# digifab.net
KiCad netlist of a schematic drawn in EAGLE
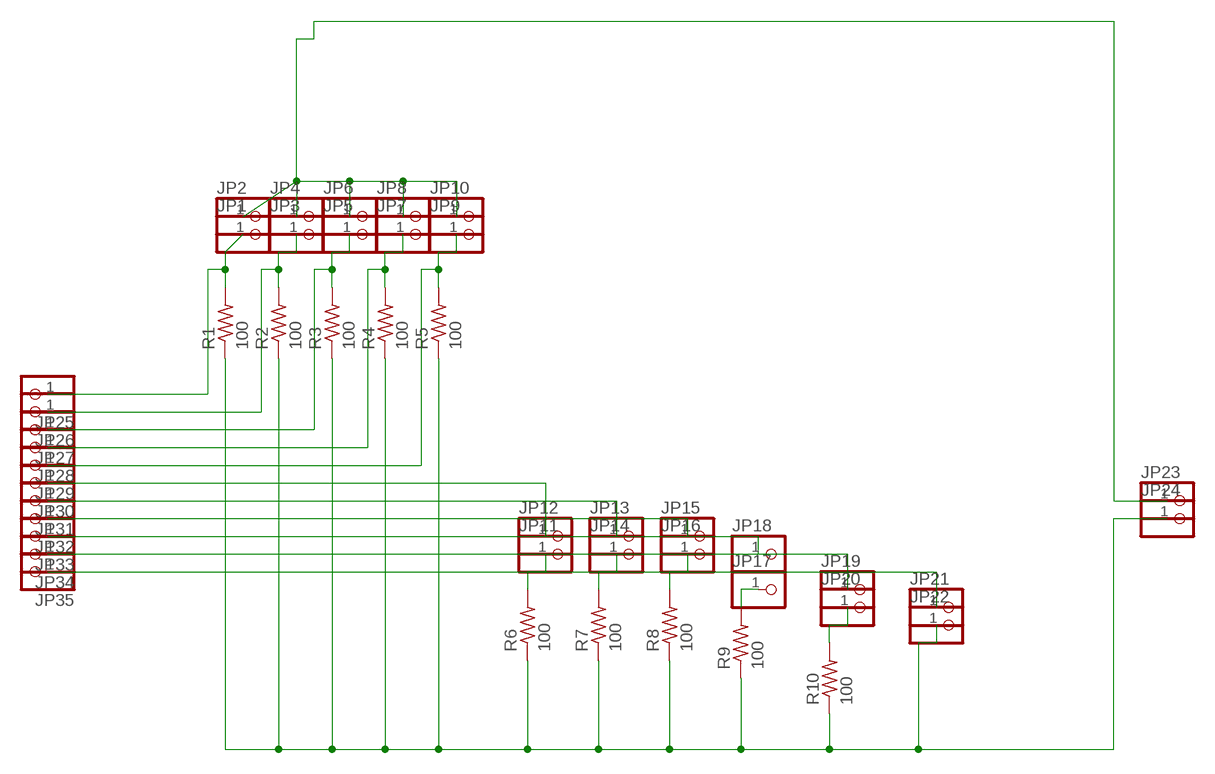
[diagram p0: schematic, sheet 1]

(export (version "E")
  (design (tool "Eeschema 10.0.6"))
  (components
    (comp (ref "JP1")
      (value "PINHD-1X01_2.54-90°")
      (footprint "eagle-import:1X01_90")
      (libsource (lib "eagle-import") (part "PINHD-1X01_2.54-90°"))
    )
    (comp (ref "JP2")
      (value "PINHD-1X01_2.54-90°")
      (footprint "eagle-import:1X01_90")
      (libsource (lib "eagle-import") (part "PINHD-1X01_2.54-90°"))
    )
    (comp (ref "JP3")
      (value "PINHD-1X01_2.54-90°")
      (footprint "eagle-import:1X01_90")
      (libsource (lib "eagle-import") (part "PINHD-1X01_2.54-90°"))
    )
    (comp (ref "JP4")
      (value "PINHD-1X01_2.54-90°")
      (footprint "eagle-import:1X01_90")
      (libsource (lib "eagle-import") (part "PINHD-1X01_2.54-90°"))
    )
    (comp (ref "JP5")
      (value "PINHD-1X01_2.54-90°")
      (footprint "eagle-import:1X01_90")
      (libsource (lib "eagle-import") (part "PINHD-1X01_2.54-90°"))
    )
    (comp (ref "JP6")
      (value "PINHD-1X01_2.54-90°")
      (footprint "eagle-import:1X01_90")
      (libsource (lib "eagle-import") (part "PINHD-1X01_2.54-90°"))
    )
    (comp (ref "JP7")
      (value "PINHD-1X01_2.54-90°")
      (footprint "eagle-import:1X01_90")
      (libsource (lib "eagle-import") (part "PINHD-1X01_2.54-90°"))
    )
    (comp (ref "JP8")
      (value "PINHD-1X01_2.54-90°")
      (footprint "eagle-import:1X01_90")
      (libsource (lib "eagle-import") (part "PINHD-1X01_2.54-90°"))
    )
    (comp (ref "JP9")
      (value "PINHD-1X01_2.54-90°")
      (footprint "eagle-import:1X01_90")
      (libsource (lib "eagle-import") (part "PINHD-1X01_2.54-90°"))
    )
    (comp (ref "JP10")
      (value "PINHD-1X01_2.54-90°")
      (footprint "eagle-import:1X01_90")
      (libsource (lib "eagle-import") (part "PINHD-1X01_2.54-90°"))
    )
    (comp (ref "JP11")
      (value "PINHD-1X01_2.54-90°")
      (footprint "eagle-import:1X01_90")
      (libsource (lib "eagle-import") (part "PINHD-1X01_2.54-90°"))
    )
    (comp (ref "JP12")
      (value "PINHD-1X01_2.54-90°")
      (footprint "eagle-import:1X01_90")
      (libsource (lib "eagle-import") (part "PINHD-1X01_2.54-90°"))
    )
    (comp (ref "JP13")
      (value "PINHD-1X01_2.54-90°")
      (footprint "eagle-import:1X01_90")
      (libsource (lib "eagle-import") (part "PINHD-1X01_2.54-90°"))
    )
    (comp (ref "JP14")
      (value "PINHD-1X01_2.54-90°")
      (footprint "eagle-import:1X01_90")
      (libsource (lib "eagle-import") (part "PINHD-1X01_2.54-90°"))
    )
    (comp (ref "JP15")
      (value "PINHD-1X01_2.54-90°")
      (footprint "eagle-import:1X01_90")
      (libsource (lib "eagle-import") (part "PINHD-1X01_2.54-90°"))
    )
    (comp (ref "JP16")
      (value "PINHD-1X01_2.54-90°")
      (footprint "eagle-import:1X01_90")
      (libsource (lib "eagle-import") (part "PINHD-1X01_2.54-90°"))
    )
    (comp (ref "JP17")
      (value "PINHD-1X01_2.54-90°")
      (footprint "eagle-import:1X01_90")
      (libsource (lib "eagle-import") (part "PINHD-1X01_2.54-90°"))
    )
    (comp (ref "JP18")
      (value "PINHD-1X01_2.54-90°")
      (footprint "eagle-import:1X01_90")
      (libsource (lib "eagle-import") (part "PINHD-1X01_2.54-90°"))
    )
    (comp (ref "JP19")
      (value "PINHD-1X01_2.54-90°")
      (footprint "eagle-import:1X01_90")
      (libsource (lib "eagle-import") (part "PINHD-1X01_2.54-90°"))
    )
    (comp (ref "JP20")
      (value "PINHD-1X01_2.54-90°")
      (footprint "eagle-import:1X01_90")
      (libsource (lib "eagle-import") (part "PINHD-1X01_2.54-90°"))
    )
    (comp (ref "JP21")
      (value "PINHD-1X01_2.54-90°")
      (footprint "eagle-import:1X01_90")
      (libsource (lib "eagle-import") (part "PINHD-1X01_2.54-90°"))
    )
    (comp (ref "JP22")
      (value "PINHD-1X01_2.54-90°")
      (footprint "eagle-import:1X01_90")
      (libsource (lib "eagle-import") (part "PINHD-1X01_2.54-90°"))
    )
    (comp (ref "JP23")
      (value "PINHD-1X01_2.54-90°")
      (footprint "eagle-import:1X01_90")
      (libsource (lib "eagle-import") (part "PINHD-1X01_2.54-90°"))
    )
    (comp (ref "JP24")
      (value "PINHD-1X01_2.54-90°")
      (footprint "eagle-import:1X01_90")
      (libsource (lib "eagle-import") (part "PINHD-1X01_2.54-90°"))
    )
    (comp (ref "JP25")
      (value "PINHD-1X01_2.54-90°")
      (footprint "eagle-import:1X01_90")
      (libsource (lib "eagle-import") (part "PINHD-1X01_2.54-90°"))
    )
    (comp (ref "JP26")
      (value "PINHD-1X01_2.54-90°")
      (footprint "eagle-import:1X01_90")
      (libsource (lib "eagle-import") (part "PINHD-1X01_2.54-90°"))
    )
    (comp (ref "JP27")
      (value "PINHD-1X01_2.54-90°")
      (footprint "eagle-import:1X01_90")
      (libsource (lib "eagle-import") (part "PINHD-1X01_2.54-90°"))
    )
    (comp (ref "JP28")
      (value "PINHD-1X01_2.54-90°")
      (footprint "eagle-import:1X01_90")
      (libsource (lib "eagle-import") (part "PINHD-1X01_2.54-90°"))
    )
    (comp (ref "JP29")
      (value "PINHD-1X01_2.54-90°")
      (footprint "eagle-import:1X01_90")
      (libsource (lib "eagle-import") (part "PINHD-1X01_2.54-90°"))
    )
    (comp (ref "JP30")
      (value "PINHD-1X01_2.54-90°")
      (footprint "eagle-import:1X01_90")
      (libsource (lib "eagle-import") (part "PINHD-1X01_2.54-90°"))
    )
    (comp (ref "JP31")
      (value "PINHD-1X01_2.54-90°")
      (footprint "eagle-import:1X01_90")
      (libsource (lib "eagle-import") (part "PINHD-1X01_2.54-90°"))
    )
    (comp (ref "JP32")
      (value "PINHD-1X01_2.54-90°")
      (footprint "eagle-import:1X01_90")
      (libsource (lib "eagle-import") (part "PINHD-1X01_2.54-90°"))
    )
    (comp (ref "JP33")
      (value "PINHD-1X01_2.54-90°")
      (footprint "eagle-import:1X01_90")
      (libsource (lib "eagle-import") (part "PINHD-1X01_2.54-90°"))
    )
    (comp (ref "JP34")
      (value "PINHD-1X01_2.54-90°")
      (footprint "eagle-import:1X01_90")
      (libsource (lib "eagle-import") (part "PINHD-1X01_2.54-90°"))
    )
    (comp (ref "JP35")
      (value "PINHD-1X01_2.54-90°")
      (footprint "eagle-import:1X01_90")
      (libsource (lib "eagle-import") (part "PINHD-1X01_2.54-90°"))
    )
    (comp (ref "R1")
      (value "100")
      (footprint "eagle-import:R1206FAB")
      (libsource (lib "eagle-import") (part "RES-US1206FAB"))
    )
    (comp (ref "R2")
      (value "100")
      (footprint "eagle-import:R1206FAB")
      (libsource (lib "eagle-import") (part "RES-US1206FAB"))
    )
    (comp (ref "R3")
      (value "100")
      (footprint "eagle-import:R1206FAB")
      (libsource (lib "eagle-import") (part "RES-US1206FAB"))
    )
    (comp (ref "R4")
      (value "100")
      (footprint "eagle-import:R1206FAB")
      (libsource (lib "eagle-import") (part "RES-US1206FAB"))
    )
    (comp (ref "R5")
      (value "100")
      (footprint "eagle-import:R1206FAB")
      (libsource (lib "eagle-import") (part "RES-US1206FAB"))
    )
    (comp (ref "R6")
      (value "100")
      (footprint "eagle-import:R1206FAB")
      (libsource (lib "eagle-import") (part "RES-US1206FAB"))
    )
    (comp (ref "R7")
      (value "100")
      (footprint "eagle-import:R1206FAB")
      (libsource (lib "eagle-import") (part "RES-US1206FAB"))
    )
    (comp (ref "R8")
      (value "100")
      (footprint "eagle-import:R1206FAB")
      (libsource (lib "eagle-import") (part "RES-US1206FAB"))
    )
    (comp (ref "R9")
      (value "100")
      (footprint "eagle-import:R1206FAB")
      (libsource (lib "eagle-import") (part "RES-US1206FAB"))
    )
    (comp (ref "R10")
      (value "100")
      (footprint "eagle-import:R1206FAB")
      (libsource (lib "eagle-import") (part "RES-US1206FAB"))
    )
  )
  (nets
    (net (code "1") (name "Net-(JP1-Pad1)") (class "Default")
      (node (ref "JP1") (pin "1") (pinfunction "1_1") (pintype "passive"))
      (node (ref "JP25") (pin "1") (pinfunction "1_1") (pintype "passive"))
      (node (ref "R1") (pin "2") (pinfunction "2_2") (pintype "passive"))
    )
    (net (code "2") (name "Net-(JP10-Pad1)") (class "Default")
      (node (ref "JP10") (pin "1") (pinfunction "1_1") (pintype "passive"))
      (node (ref "JP2") (pin "1") (pinfunction "1_1") (pintype "passive"))
      (node (ref "JP23") (pin "1") (pinfunction "1_1") (pintype "passive"))
      (node (ref "JP4") (pin "1") (pinfunction "1_1") (pintype "passive"))
      (node (ref "JP6") (pin "1") (pinfunction "1_1") (pintype "passive"))
      (node (ref "JP8") (pin "1") (pinfunction "1_1") (pintype "passive"))
    )
    (net (code "3") (name "Net-(JP11-Pad1)") (class "Default")
      (node (ref "JP11") (pin "1") (pinfunction "1_1") (pintype "passive"))
      (node (ref "R6") (pin "2") (pinfunction "2_2") (pintype "passive"))
    )
    (net (code "4") (name "Net-(JP12-Pad1)") (class "Default")
      (node (ref "JP12") (pin "1") (pinfunction "1_1") (pintype "passive"))
      (node (ref "JP30") (pin "1") (pinfunction "1_1") (pintype "passive"))
    )
    (net (code "5") (name "Net-(JP13-Pad1)") (class "Default")
      (node (ref "JP13") (pin "1") (pinfunction "1_1") (pintype "passive"))
      (node (ref "JP31") (pin "1") (pinfunction "1_1") (pintype "passive"))
    )
    (net (code "6") (name "Net-(JP14-Pad1)") (class "Default")
      (node (ref "JP14") (pin "1") (pinfunction "1_1") (pintype "passive"))
      (node (ref "R7") (pin "2") (pinfunction "2_2") (pintype "passive"))
    )
    (net (code "7") (name "Net-(JP15-Pad1)") (class "Default")
      (node (ref "JP15") (pin "1") (pinfunction "1_1") (pintype "passive"))
      (node (ref "JP32") (pin "1") (pinfunction "1_1") (pintype "passive"))
    )
    (net (code "8") (name "Net-(JP16-Pad1)") (class "Default")
      (node (ref "JP16") (pin "1") (pinfunction "1_1") (pintype "passive"))
      (node (ref "R8") (pin "2") (pinfunction "2_2") (pintype "passive"))
    )
    (net (code "9") (name "Net-(JP17-Pad1)") (class "Default")
      (node (ref "JP17") (pin "1") (pinfunction "1_1") (pintype "passive"))
      (node (ref "R9") (pin "2") (pinfunction "2_2") (pintype "passive"))
    )
    (net (code "10") (name "Net-(JP18-Pad1)") (class "Default")
      (node (ref "JP18") (pin "1") (pinfunction "1_1") (pintype "passive"))
      (node (ref "JP33") (pin "1") (pinfunction "1_1") (pintype "passive"))
    )
    (net (code "11") (name "Net-(JP19-Pad1)") (class "Default")
      (node (ref "JP19") (pin "1") (pinfunction "1_1") (pintype "passive"))
      (node (ref "JP34") (pin "1") (pinfunction "1_1") (pintype "passive"))
    )
    (net (code "12") (name "Net-(JP20-Pad1)") (class "Default")
      (node (ref "JP20") (pin "1") (pinfunction "1_1") (pintype "passive"))
      (node (ref "R10") (pin "2") (pinfunction "2_2") (pintype "passive"))
    )
    (net (code "13") (name "Net-(JP21-Pad1)") (class "Default")
      (node (ref "JP21") (pin "1") (pinfunction "1_1") (pintype "passive"))
      (node (ref "JP35") (pin "1") (pinfunction "1_1") (pintype "passive"))
    )
    (net (code "14") (name "Net-(JP22-Pad1)") (class "Default")
      (node (ref "JP22") (pin "1") (pinfunction "1_1") (pintype "passive"))
      (node (ref "JP24") (pin "1") (pinfunction "1_1") (pintype "passive"))
      (node (ref "R1") (pin "1") (pinfunction "1_1") (pintype "passive"))
      (node (ref "R10") (pin "1") (pinfunction "1_1") (pintype "passive"))
      (node (ref "R2") (pin "1") (pinfunction "1_1") (pintype "passive"))
      (node (ref "R3") (pin "1") (pinfunction "1_1") (pintype "passive"))
      (node (ref "R4") (pin "1") (pinfunction "1_1") (pintype "passive"))
      (node (ref "R5") (pin "1") (pinfunction "1_1") (pintype "passive"))
      (node (ref "R6") (pin "1") (pinfunction "1_1") (pintype "passive"))
      (node (ref "R7") (pin "1") (pinfunction "1_1") (pintype "passive"))
      (node (ref "R8") (pin "1") (pinfunction "1_1") (pintype "passive"))
      (node (ref "R9") (pin "1") (pinfunction "1_1") (pintype "passive"))
    )
    (net (code "15") (name "Net-(JP26-Pad1)") (class "Default")
      (node (ref "JP26") (pin "1") (pinfunction "1_1") (pintype "passive"))
      (node (ref "JP3") (pin "1") (pinfunction "1_1") (pintype "passive"))
      (node (ref "R2") (pin "2") (pinfunction "2_2") (pintype "passive"))
    )
    (net (code "16") (name "Net-(JP27-Pad1)") (class "Default")
      (node (ref "JP27") (pin "1") (pinfunction "1_1") (pintype "passive"))
      (node (ref "JP5") (pin "1") (pinfunction "1_1") (pintype "passive"))
      (node (ref "R3") (pin "2") (pinfunction "2_2") (pintype "passive"))
    )
    (net (code "17") (name "Net-(JP28-Pad1)") (class "Default")
      (node (ref "JP28") (pin "1") (pinfunction "1_1") (pintype "passive"))
      (node (ref "JP7") (pin "1") (pinfunction "1_1") (pintype "passive"))
      (node (ref "R4") (pin "2") (pinfunction "2_2") (pintype "passive"))
    )
    (net (code "18") (name "Net-(JP29-Pad1)") (class "Default")
      (node (ref "JP29") (pin "1") (pinfunction "1_1") (pintype "passive"))
      (node (ref "JP9") (pin "1") (pinfunction "1_1") (pintype "passive"))
      (node (ref "R5") (pin "2") (pinfunction "2_2") (pintype "passive"))
    )
  )
)
